# ASD2501.net
KiCad netlist of a schematic drawn in EAGLE
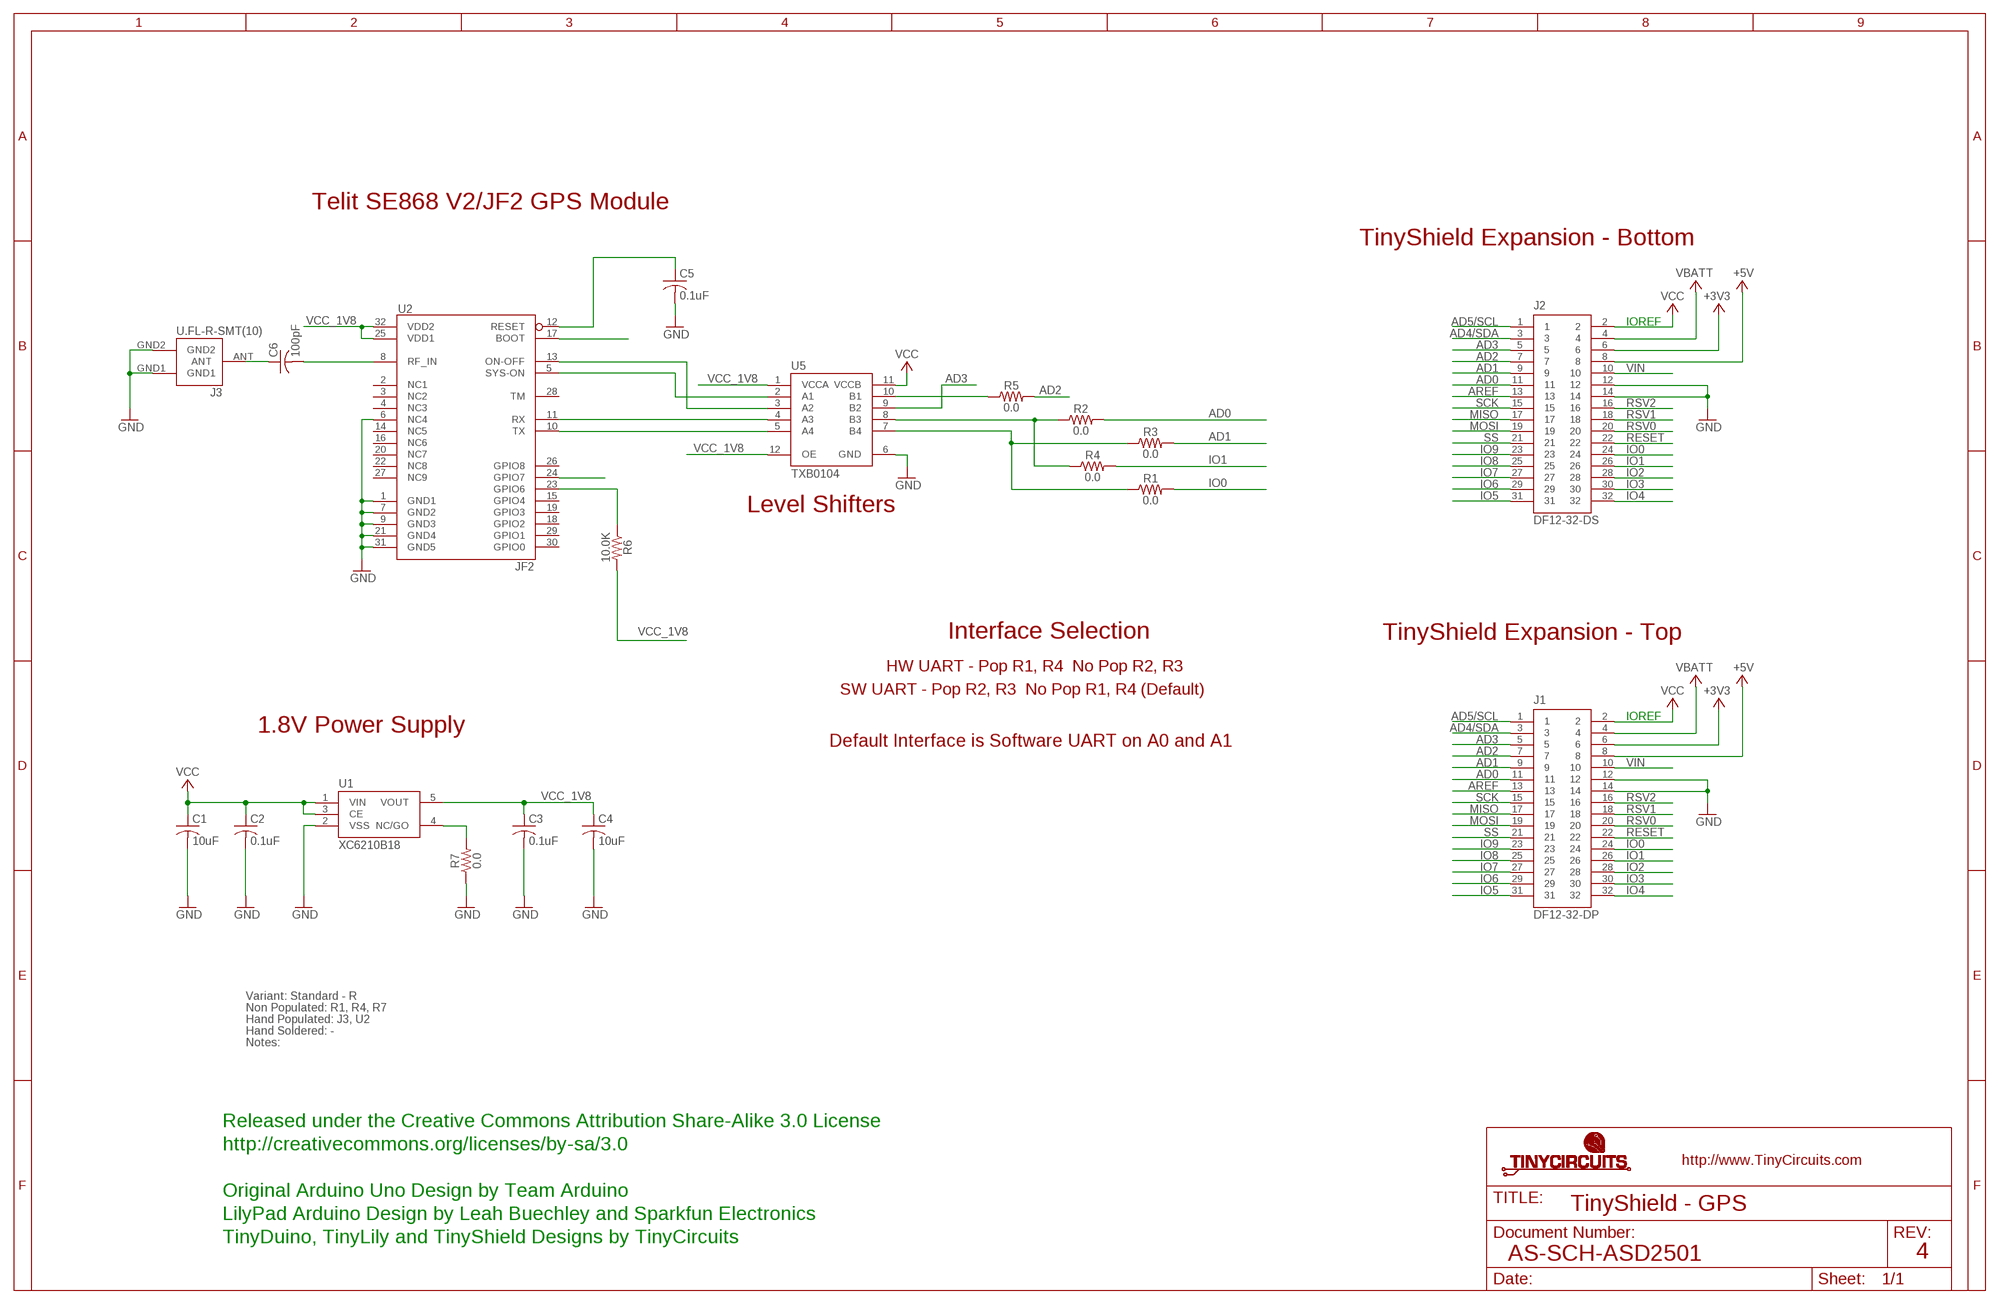
[diagram p0: schematic, sheet 1]

(export (version "E")
  (design (tool "Eeschema 10.0.6"))
  (components
    (comp (ref "C1")
      (value "10uF")
      (footprint "eagle-import:C0805")
      (fields (field (name "PARTNO") "AS-ITM-00045") (field (name "PARTNO_1") "AS-ITM-00045"))
      (libsource (lib "eagle-import") (part "AS-ITM-00045"))
    )
    (comp (ref "C2")
      (value "0.1uF")
      (footprint "eagle-import:C0402")
      (fields (field (name "PARTNO") "AS-ITM-00008") (field (name "PARTNO_1") "AS-ITM-00008"))
      (libsource (lib "eagle-import") (part "AS-ITM-00008"))
    )
    (comp (ref "C3")
      (value "0.1uF")
      (footprint "eagle-import:C0402")
      (fields (field (name "PARTNO") "AS-ITM-00008") (field (name "PARTNO_1") "AS-ITM-00008"))
      (libsource (lib "eagle-import") (part "AS-ITM-00008"))
    )
    (comp (ref "C4")
      (value "10uF")
      (footprint "eagle-import:C0805")
      (fields (field (name "PARTNO") "AS-ITM-00045") (field (name "PARTNO_1") "AS-ITM-00045"))
      (libsource (lib "eagle-import") (part "AS-ITM-00045"))
    )
    (comp (ref "C5")
      (value "0.1uF")
      (footprint "eagle-import:C0402")
      (fields (field (name "PARTNO") "AS-ITM-00008") (field (name "PARTNO_1") "AS-ITM-00008"))
      (libsource (lib "eagle-import") (part "AS-ITM-00008"))
    )
    (comp (ref "C6")
      (value "100pF")
      (footprint "eagle-import:0402")
      (fields (field (name "PARTNO") "AS-ITM-00148") (field (name "PARTNO_1") "AS-ITM-00148"))
      (libsource (lib "eagle-import") (part "AS-ITM-00148"))
    )
    (comp (ref "J1")
      (value "DF12-32-DP")
      (footprint "eagle-import:DF12-32-DP")
      (fields (field (name "PARTNO") "AS-ITM-00015") (field (name "PARTNO_1") "AS-ITM-00015"))
      (libsource (lib "eagle-import") (part "AS-ITM-00015"))
    )
    (comp (ref "J2")
      (value "DF12-32-DS")
      (footprint "eagle-import:DF12-32-DS")
      (fields (field (name "PARTNO") "AS-ITM-00012") (field (name "PARTNO_1") "AS-ITM-00012"))
      (libsource (lib "eagle-import") (part "AS-ITM-00012"))
    )
    (comp (ref "J3")
      (value "U.FL-R-SMT(10)")
      (footprint "eagle-import:U.FL-R-SMT(10)")
      (fields (field (name "PARTNO") "AS-ITM-00193"))
      (libsource (lib "eagle-import") (part "AS-ITM-00193"))
    )
    (comp (ref "R1")
      (value "0.0")
      (footprint "eagle-import:0402")
      (fields (field (name "PARTNO") "AS-ITM-00076"))
      (libsource (lib "eagle-import") (part "AS-ITM-00076"))
    )
    (comp (ref "R2")
      (value "0.0")
      (footprint "eagle-import:0402")
      (fields (field (name "PARTNO") "AS-ITM-00076"))
      (libsource (lib "eagle-import") (part "AS-ITM-00076"))
    )
    (comp (ref "R3")
      (value "0.0")
      (footprint "eagle-import:0402")
      (fields (field (name "PARTNO") "AS-ITM-00076"))
      (libsource (lib "eagle-import") (part "AS-ITM-00076"))
    )
    (comp (ref "R4")
      (value "0.0")
      (footprint "eagle-import:0402")
      (fields (field (name "PARTNO") "AS-ITM-00076"))
      (libsource (lib "eagle-import") (part "AS-ITM-00076"))
    )
    (comp (ref "R5")
      (value "0.0")
      (footprint "eagle-import:0402")
      (fields (field (name "PARTNO") "AS-ITM-00076") (field (name "PARTNO_1") "AS-ITM-00076"))
      (libsource (lib "eagle-import") (part "AS-ITM-00076"))
    )
    (comp (ref "R6")
      (value "10.0K")
      (footprint "eagle-import:0402")
      (fields (field (name "PARTNO") "AS-ITM-00032"))
      (libsource (lib "eagle-import") (part "AS-ITM-00032"))
    )
    (comp (ref "R7")
      (value "0.0")
      (footprint "eagle-import:0402")
      (fields (field (name "PARTNO") "AS-ITM-00076") (field (name "PARTNO_1") "AS-ITM-00076"))
      (libsource (lib "eagle-import") (part "AS-ITM-00076"))
    )
    (comp (ref "U1")
      (value "XC6210B18")
      (footprint "eagle-import:SOT-25")
      (fields (field (name "PARTNO") "AS-ITM-00075") (field (name "PARTNO_1") "AS-ITM-00075"))
      (libsource (lib "eagle-import") (part "AS-ITM-00075"))
    )
    (comp (ref "U2")
      (value "JF2")
      (footprint "eagle-import:JF2")
      (fields (field (name "PARTNO") "AS-ITM-00077"))
      (libsource (lib "eagle-import") (part "AS-ITM-00077"))
    )
    (comp (ref "U5")
      (value "TXB0104")
      (footprint "eagle-import:UQFN-12")
      (fields (field (name "PARTNO") "AS-ITM-00048"))
      (libsource (lib "eagle-import") (part "AS-ITM-00048"))
    )
  )
  (nets
    (net (code "1") (name "+3V3") (class "Default")
      (node (ref "J1") (pin "6") (pinfunction "6_6") (pintype "bidirectional"))
      (node (ref "J2") (pin "6") (pinfunction "6_6") (pintype "bidirectional"))
    )
    (net (code "2") (name "+5V") (class "Default")
      (node (ref "J1") (pin "8") (pinfunction "8_8") (pintype "bidirectional"))
      (node (ref "J2") (pin "8") (pinfunction "8_8") (pintype "bidirectional"))
    )
    (net (code "3") (name "/AD0") (class "Default")
      (node (ref "J1") (pin "11") (pinfunction "11_11") (pintype "bidirectional"))
      (node (ref "J2") (pin "11") (pinfunction "11_11") (pintype "bidirectional"))
      (node (ref "R2") (pin "2") (pinfunction "2_2") (pintype "passive"))
    )
    (net (code "4") (name "/AD1") (class "Default")
      (node (ref "J1") (pin "9") (pinfunction "9_9") (pintype "bidirectional"))
      (node (ref "J2") (pin "9") (pinfunction "9_9") (pintype "bidirectional"))
      (node (ref "R3") (pin "2") (pinfunction "2_2") (pintype "passive"))
    )
    (net (code "5") (name "/AD2") (class "Default")
      (node (ref "J1") (pin "7") (pinfunction "7_7") (pintype "bidirectional"))
      (node (ref "J2") (pin "7") (pinfunction "7_7") (pintype "bidirectional"))
      (node (ref "R5") (pin "2") (pinfunction "2_2") (pintype "passive"))
    )
    (net (code "6") (name "/AD3") (class "Default")
      (node (ref "J1") (pin "5") (pinfunction "5_5") (pintype "bidirectional"))
      (node (ref "J2") (pin "5") (pinfunction "5_5") (pintype "bidirectional"))
      (node (ref "U5") (pin "9") (pinfunction "B2_9") (pintype "bidirectional"))
    )
    (net (code "7") (name "/AD4{slash}SDA") (class "Default")
      (node (ref "J1") (pin "3") (pinfunction "3_3") (pintype "bidirectional"))
      (node (ref "J2") (pin "3") (pinfunction "3_3") (pintype "bidirectional"))
    )
    (net (code "8") (name "/AD5{slash}SCL") (class "Default")
      (node (ref "J1") (pin "1") (pinfunction "1_1") (pintype "bidirectional"))
      (node (ref "J2") (pin "1") (pinfunction "1_1") (pintype "bidirectional"))
    )
    (net (code "9") (name "/AREF") (class "Default")
      (node (ref "J1") (pin "13") (pinfunction "13_13") (pintype "bidirectional"))
      (node (ref "J2") (pin "13") (pinfunction "13_13") (pintype "bidirectional"))
    )
    (net (code "10") (name "/IO0") (class "Default")
      (node (ref "J1") (pin "24") (pinfunction "24_24") (pintype "bidirectional"))
      (node (ref "J2") (pin "24") (pinfunction "24_24") (pintype "bidirectional"))
      (node (ref "R1") (pin "2") (pinfunction "2_2") (pintype "passive"))
    )
    (net (code "11") (name "/IO1") (class "Default")
      (node (ref "J1") (pin "26") (pinfunction "26_26") (pintype "bidirectional"))
      (node (ref "J2") (pin "26") (pinfunction "26_26") (pintype "bidirectional"))
      (node (ref "R4") (pin "2") (pinfunction "2_2") (pintype "passive"))
    )
    (net (code "12") (name "/IO2") (class "Default")
      (node (ref "J1") (pin "28") (pinfunction "28_28") (pintype "bidirectional"))
      (node (ref "J2") (pin "28") (pinfunction "28_28") (pintype "bidirectional"))
    )
    (net (code "13") (name "/IO3") (class "Default")
      (node (ref "J1") (pin "30") (pinfunction "30_30") (pintype "bidirectional"))
      (node (ref "J2") (pin "30") (pinfunction "30_30") (pintype "bidirectional"))
    )
    (net (code "14") (name "/IO4") (class "Default")
      (node (ref "J1") (pin "32") (pinfunction "32_32") (pintype "bidirectional"))
      (node (ref "J2") (pin "32") (pinfunction "32_32") (pintype "bidirectional"))
    )
    (net (code "15") (name "/IO5") (class "Default")
      (node (ref "J1") (pin "31") (pinfunction "31_31") (pintype "bidirectional"))
      (node (ref "J2") (pin "31") (pinfunction "31_31") (pintype "bidirectional"))
    )
    (net (code "16") (name "/IO6") (class "Default")
      (node (ref "J1") (pin "29") (pinfunction "29_29") (pintype "bidirectional"))
      (node (ref "J2") (pin "29") (pinfunction "29_29") (pintype "bidirectional"))
    )
    (net (code "17") (name "/IO7") (class "Default")
      (node (ref "J1") (pin "27") (pinfunction "27_27") (pintype "bidirectional"))
      (node (ref "J2") (pin "27") (pinfunction "27_27") (pintype "bidirectional"))
    )
    (net (code "18") (name "/IO8") (class "Default")
      (node (ref "J1") (pin "25") (pinfunction "25_25") (pintype "bidirectional"))
      (node (ref "J2") (pin "25") (pinfunction "25_25") (pintype "bidirectional"))
    )
    (net (code "19") (name "/IO9") (class "Default")
      (node (ref "J1") (pin "23") (pinfunction "23_23") (pintype "bidirectional"))
      (node (ref "J2") (pin "23") (pinfunction "23_23") (pintype "bidirectional"))
    )
    (net (code "20") (name "/MISO") (class "Default")
      (node (ref "J1") (pin "17") (pinfunction "17_17") (pintype "bidirectional"))
      (node (ref "J2") (pin "17") (pinfunction "17_17") (pintype "bidirectional"))
    )
    (net (code "21") (name "/MOSI") (class "Default")
      (node (ref "J1") (pin "19") (pinfunction "19_19") (pintype "bidirectional"))
      (node (ref "J2") (pin "19") (pinfunction "19_19") (pintype "bidirectional"))
    )
    (net (code "22") (name "/RESET") (class "Default")
      (node (ref "J1") (pin "22") (pinfunction "22_22") (pintype "bidirectional"))
      (node (ref "J2") (pin "22") (pinfunction "22_22") (pintype "bidirectional"))
    )
    (net (code "23") (name "/RSV0") (class "Default")
      (node (ref "J1") (pin "20") (pinfunction "20_20") (pintype "bidirectional"))
      (node (ref "J2") (pin "20") (pinfunction "20_20") (pintype "bidirectional"))
    )
    (net (code "24") (name "/RSV1") (class "Default")
      (node (ref "J1") (pin "18") (pinfunction "18_18") (pintype "bidirectional"))
      (node (ref "J2") (pin "18") (pinfunction "18_18") (pintype "bidirectional"))
    )
    (net (code "25") (name "/RSV2") (class "Default")
      (node (ref "J1") (pin "16") (pinfunction "16_16") (pintype "bidirectional"))
      (node (ref "J2") (pin "16") (pinfunction "16_16") (pintype "bidirectional"))
    )
    (net (code "26") (name "/SCK") (class "Default")
      (node (ref "J1") (pin "15") (pinfunction "15_15") (pintype "bidirectional"))
      (node (ref "J2") (pin "15") (pinfunction "15_15") (pintype "bidirectional"))
    )
    (net (code "27") (name "/SS") (class "Default")
      (node (ref "J1") (pin "21") (pinfunction "21_21") (pintype "bidirectional"))
      (node (ref "J2") (pin "21") (pinfunction "21_21") (pintype "bidirectional"))
    )
    (net (code "28") (name "/VCC_1V8") (class "Default")
      (node (ref "C3") (pin "1") (pinfunction "1_1") (pintype "passive"))
      (node (ref "C4") (pin "1") (pinfunction "1_1") (pintype "passive"))
      (node (ref "R6") (pin "2") (pinfunction "2_2") (pintype "passive"))
      (node (ref "U1") (pin "5") (pinfunction "VOUT_5") (pintype "bidirectional"))
      (node (ref "U2") (pin "25") (pinfunction "VDD1_25") (pintype "power_in"))
      (node (ref "U2") (pin "32") (pinfunction "VDD2_32") (pintype "power_in"))
      (node (ref "U5") (pin "1") (pinfunction "VCCA_1") (pintype "bidirectional"))
      (node (ref "U5") (pin "12") (pinfunction "OE_12") (pintype "bidirectional"))
    )
    (net (code "29") (name "/VIN") (class "Default")
      (node (ref "J1") (pin "10") (pinfunction "10_10") (pintype "bidirectional"))
      (node (ref "J2") (pin "10") (pinfunction "10_10") (pintype "bidirectional"))
    )
    (net (code "30") (name "GND") (class "Default")
      (node (ref "C1") (pin "2") (pinfunction "2_2") (pintype "passive"))
      (node (ref "C2") (pin "2") (pinfunction "2_2") (pintype "passive"))
      (node (ref "C3") (pin "2") (pinfunction "2_2") (pintype "passive"))
      (node (ref "C4") (pin "2") (pinfunction "2_2") (pintype "passive"))
      (node (ref "C5") (pin "2") (pinfunction "2_2") (pintype "passive"))
      (node (ref "J1") (pin "12") (pinfunction "12_12") (pintype "bidirectional"))
      (node (ref "J1") (pin "14") (pinfunction "14_14") (pintype "bidirectional"))
      (node (ref "J2") (pin "12") (pinfunction "12_12") (pintype "bidirectional"))
      (node (ref "J2") (pin "14") (pinfunction "14_14") (pintype "bidirectional"))
      (node (ref "J3") (pin "GND1") (pinfunction "GND1_GND1") (pintype "bidirectional"))
      (node (ref "J3") (pin "GND2") (pinfunction "GND2_GND2") (pintype "bidirectional"))
      (node (ref "R7") (pin "1") (pinfunction "1_1") (pintype "passive"))
      (node (ref "U1") (pin "2") (pinfunction "VSS_2") (pintype "power_in"))
      (node (ref "U2") (pin "1") (pinfunction "GND1_1") (pintype "power_in"))
      (node (ref "U2") (pin "21") (pinfunction "GND4_21") (pintype "power_in"))
      (node (ref "U2") (pin "31") (pinfunction "GND5_31") (pintype "power_in"))
      (node (ref "U2") (pin "6") (pinfunction "NC4_6") (pintype "bidirectional"))
      (node (ref "U2") (pin "7") (pinfunction "GND2_7") (pintype "power_in"))
      (node (ref "U2") (pin "9") (pinfunction "GND3_9") (pintype "power_in"))
      (node (ref "U5") (pin "6") (pinfunction "GND_6") (pintype "bidirectional"))
    )
    (net (code "31") (name "Net-(C6-Pad1)") (class "Default")
      (node (ref "C6") (pin "1") (pinfunction "1_1") (pintype "passive"))
      (node (ref "J3") (pin "ANT") (pinfunction "ANT_ANT") (pintype "bidirectional"))
    )
    (net (code "32") (name "Net-(U1-NC{slash}GO)") (class "Default")
      (node (ref "R7") (pin "2") (pinfunction "2_2") (pintype "passive"))
      (node (ref "U1") (pin "4") (pinfunction "NC/GO_4") (pintype "bidirectional"))
    )
    (net (code "33") (name "Net-(U2-GPIO6)") (class "Default")
      (node (ref "R6") (pin "1") (pinfunction "1_1") (pintype "passive"))
      (node (ref "U2") (pin "23") (pinfunction "GPIO6_23") (pintype "bidirectional"))
    )
    (net (code "34") (name "Net-(U2-ON-OFF)") (class "Default")
      (node (ref "U2") (pin "13") (pinfunction "ON-OFF_13") (pintype "bidirectional"))
      (node (ref "U5") (pin "3") (pinfunction "A2_3") (pintype "bidirectional"))
    )
    (net (code "35") (name "Net-(U2-RESET)") (class "Default")
      (node (ref "C5") (pin "1") (pinfunction "1_1") (pintype "passive"))
      (node (ref "U2") (pin "12") (pinfunction "RESET_12") (pintype "bidirectional"))
    )
    (net (code "36") (name "Net-(U2-RF_IN)") (class "Default")
      (node (ref "C6") (pin "2") (pinfunction "2_2") (pintype "passive"))
      (node (ref "U2") (pin "8") (pinfunction "RF_IN_8") (pintype "bidirectional"))
    )
    (net (code "37") (name "Net-(U2-RX)") (class "Default")
      (node (ref "U2") (pin "11") (pinfunction "RX_11") (pintype "bidirectional"))
      (node (ref "U5") (pin "4") (pinfunction "A3_4") (pintype "bidirectional"))
    )
    (net (code "38") (name "Net-(U2-SYS-ON)") (class "Default")
      (node (ref "U2") (pin "5") (pinfunction "SYS-ON_5") (pintype "bidirectional"))
      (node (ref "U5") (pin "2") (pinfunction "A1_2") (pintype "bidirectional"))
    )
    (net (code "39") (name "Net-(U2-TX)") (class "Default")
      (node (ref "U2") (pin "10") (pinfunction "TX_10") (pintype "bidirectional"))
      (node (ref "U5") (pin "5") (pinfunction "A4_5") (pintype "bidirectional"))
    )
    (net (code "40") (name "Net-(U5-B1)") (class "Default")
      (node (ref "R5") (pin "1") (pinfunction "1_1") (pintype "passive"))
      (node (ref "U5") (pin "10") (pinfunction "B1_10") (pintype "bidirectional"))
    )
    (net (code "41") (name "Net-(U5-B3)") (class "Default")
      (node (ref "R2") (pin "1") (pinfunction "1_1") (pintype "passive"))
      (node (ref "R4") (pin "1") (pinfunction "1_1") (pintype "passive"))
      (node (ref "U5") (pin "8") (pinfunction "B3_8") (pintype "bidirectional"))
    )
    (net (code "42") (name "Net-(U5-B4)") (class "Default")
      (node (ref "R1") (pin "1") (pinfunction "1_1") (pintype "passive"))
      (node (ref "R3") (pin "1") (pinfunction "1_1") (pintype "passive"))
      (node (ref "U5") (pin "7") (pinfunction "B4_7") (pintype "bidirectional"))
    )
    (net (code "43") (name "VBATT") (class "Default")
      (node (ref "J1") (pin "4") (pinfunction "4_4") (pintype "bidirectional"))
      (node (ref "J2") (pin "4") (pinfunction "4_4") (pintype "bidirectional"))
    )
    (net (code "44") (name "VCC") (class "Default")
      (node (ref "C1") (pin "1") (pinfunction "1_1") (pintype "passive"))
      (node (ref "C2") (pin "1") (pinfunction "1_1") (pintype "passive"))
      (node (ref "J1") (pin "2") (pinfunction "2_2") (pintype "bidirectional"))
      (node (ref "J2") (pin "2") (pinfunction "2_2") (pintype "bidirectional"))
      (node (ref "U1") (pin "1") (pinfunction "VIN_1") (pintype "bidirectional"))
      (node (ref "U1") (pin "3") (pinfunction "CE_3") (pintype "bidirectional"))
      (node (ref "U5") (pin "11") (pinfunction "VCCB_11") (pintype "bidirectional"))
    )
    (net (code "45") (name "unconnected-(U2-BOOT-Pad17)") (class "Default")
      (node (ref "U2") (pin "17") (pinfunction "BOOT_17") (pintype "bidirectional"))
    )
    (net (code "46") (name "unconnected-(U2-GPIO0-Pad30)") (class "Default")
      (node (ref "U2") (pin "30") (pinfunction "GPIO0_30") (pintype "bidirectional"))
    )
    (net (code "47") (name "unconnected-(U2-GPIO1-Pad29)") (class "Default")
      (node (ref "U2") (pin "29") (pinfunction "GPIO1_29") (pintype "bidirectional"))
    )
    (net (code "48") (name "unconnected-(U2-GPIO2-Pad18)") (class "Default")
      (node (ref "U2") (pin "18") (pinfunction "GPIO2_18") (pintype "bidirectional"))
    )
    (net (code "49") (name "unconnected-(U2-GPIO3-Pad19)") (class "Default")
      (node (ref "U2") (pin "19") (pinfunction "GPIO3_19") (pintype "bidirectional"))
    )
    (net (code "50") (name "unconnected-(U2-GPIO4-Pad15)") (class "Default")
      (node (ref "U2") (pin "15") (pinfunction "GPIO4_15") (pintype "bidirectional"))
    )
    (net (code "51") (name "unconnected-(U2-GPIO7-Pad24)") (class "Default")
      (node (ref "U2") (pin "24") (pinfunction "GPIO7_24") (pintype "bidirectional"))
    )
    (net (code "52") (name "unconnected-(U2-GPIO8-Pad26)") (class "Default")
      (node (ref "U2") (pin "26") (pinfunction "GPIO8_26") (pintype "bidirectional"))
    )
    (net (code "53") (name "unconnected-(U2-NC1-Pad2)") (class "Default")
      (node (ref "U2") (pin "2") (pinfunction "NC1_2") (pintype "bidirectional"))
    )
    (net (code "54") (name "unconnected-(U2-NC2-Pad3)") (class "Default")
      (node (ref "U2") (pin "3") (pinfunction "NC2_3") (pintype "bidirectional"))
    )
    (net (code "55") (name "unconnected-(U2-NC3-Pad4)") (class "Default")
      (node (ref "U2") (pin "4") (pinfunction "NC3_4") (pintype "bidirectional"))
    )
    (net (code "56") (name "unconnected-(U2-NC5-Pad14)") (class "Default")
      (node (ref "U2") (pin "14") (pinfunction "NC5_14") (pintype "bidirectional"))
    )
    (net (code "57") (name "unconnected-(U2-NC6-Pad16)") (class "Default")
      (node (ref "U2") (pin "16") (pinfunction "NC6_16") (pintype "bidirectional"))
    )
    (net (code "58") (name "unconnected-(U2-NC7-Pad20)") (class "Default")
      (node (ref "U2") (pin "20") (pinfunction "NC7_20") (pintype "bidirectional"))
    )
    (net (code "59") (name "unconnected-(U2-NC8-Pad22)") (class "Default")
      (node (ref "U2") (pin "22") (pinfunction "NC8_22") (pintype "bidirectional"))
    )
    (net (code "60") (name "unconnected-(U2-NC9-Pad27)") (class "Default")
      (node (ref "U2") (pin "27") (pinfunction "NC9_27") (pintype "bidirectional"))
    )
    (net (code "61") (name "unconnected-(U2-TM-Pad28)") (class "Default")
      (node (ref "U2") (pin "28") (pinfunction "TM_28") (pintype "bidirectional"))
    )
  )
)
